# PX4FMUv2_4_6_2.net
KiCad netlist of a schematic drawn in Altium Designer
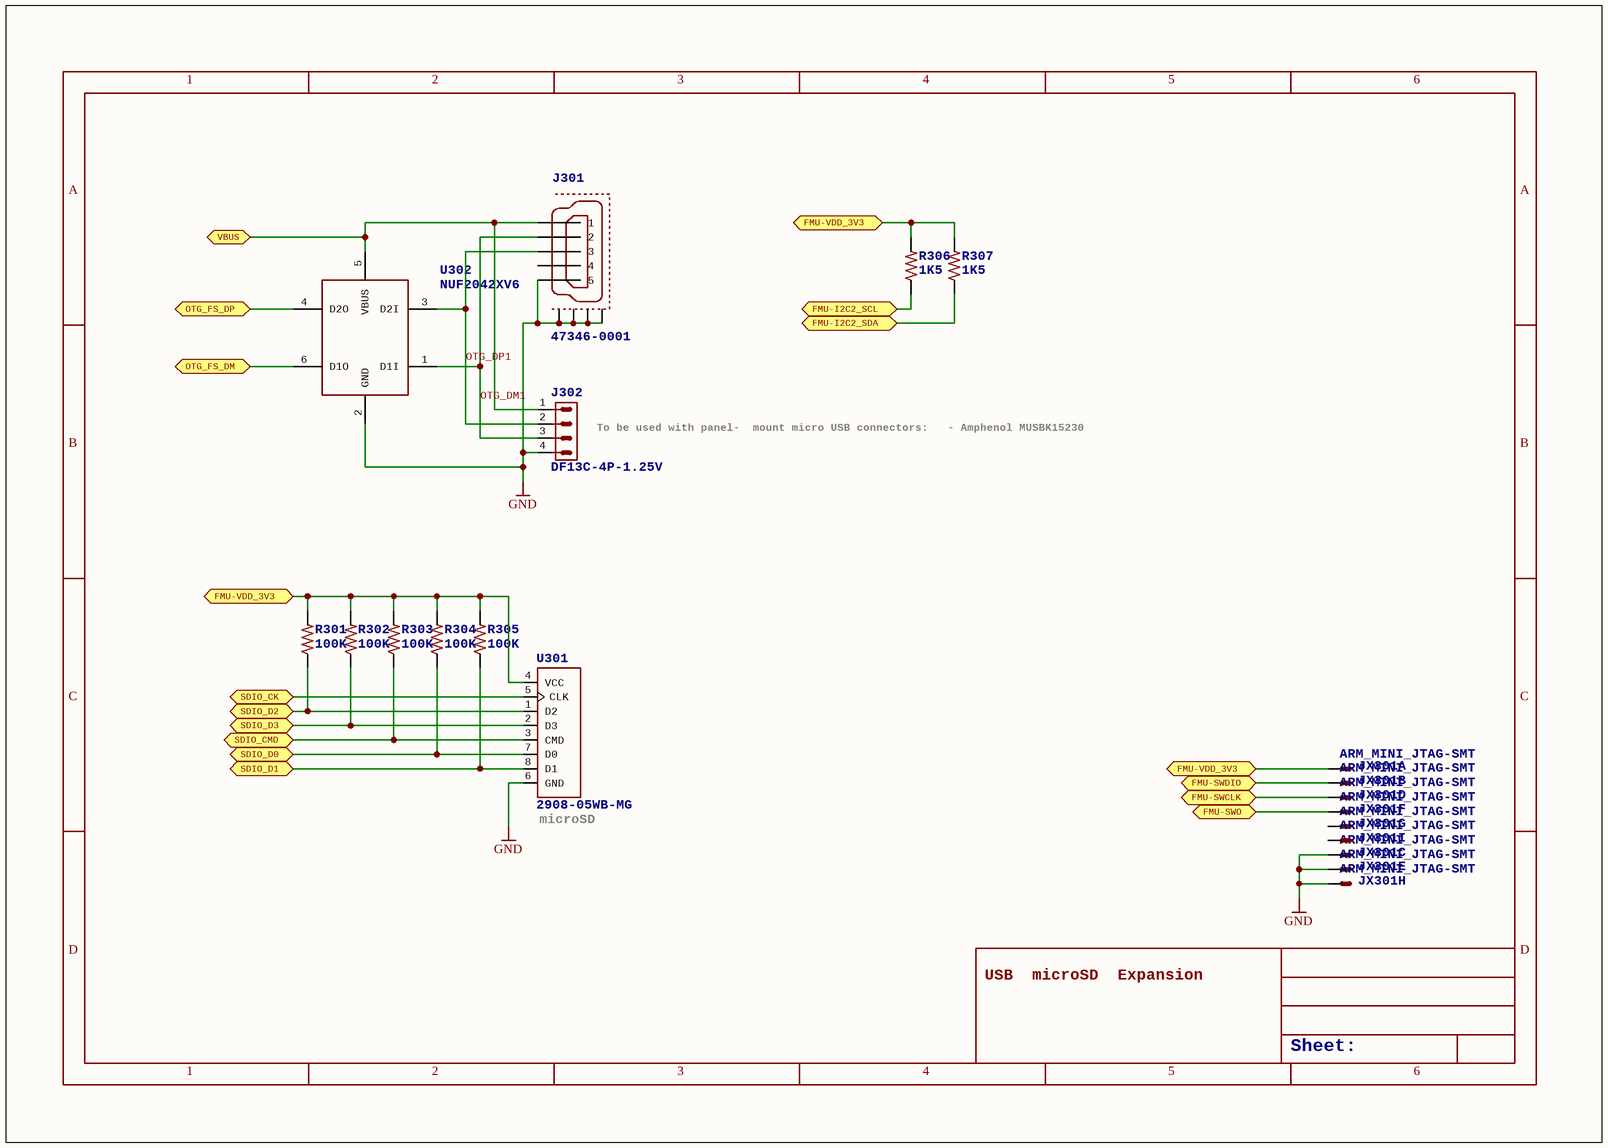
[diagram p0: PX4FMUv2.4.6_2.SchDoc]

(export (version "E")
  (design (tool "Eeschema 10.0.6"))
  (components
    (comp (ref "J301")
      (value "47346-0001")
      (footprint "MOLEX-47346-0001")
      (description "MICRO USB B, BOTTOM MOUNT")
      (libsource (lib "pixhawk2") (part "MOLEX-47346-0001"))
    )
    (comp (ref "J302")
      (value "DF13C-4P-1.25V")
      (footprint "DF13C-4P-1.25V")
      (description "DF13-4P 1.25mm Pitch Miniature Crimping Connector.")
      (fields (field (name "PARTNO") "DF13C-4P-1.25V(20)"))
      (libsource (lib "con-hirose-df13") (part "DF13-4P-1.25V"))
    )
    (comp (ref "JX301")
      (value "ARM_MINI_JTAG-SMT")
      (footprint "FTSH-105-01-XXX-DV-K")
      (description "CONNECTOR   wire to board 1.25 mm (.049 inch) pitch header")
      (fields (field (name "PARTNO") "M50-3900542"))
      (libsource (lib "pixhawk2") (part "ARM_MINI_JTAG-SMT"))
    )
    (comp (ref "R301")
      (value "100K")
      (footprint "0402-RES")
      (fields (field (name "PARTNO") "RC0402FR-07100KL"))
      (libsource (lib "pixhawk2") (part "RESISTOR0402-RES"))
    )
    (comp (ref "R302")
      (value "100K")
      (footprint "0402-RES")
      (fields (field (name "PARTNO") "RC0402FR-07100KL"))
      (libsource (lib "pixhawk2") (part "RESISTOR0402-RES"))
    )
    (comp (ref "R303")
      (value "100K")
      (footprint "0402-RES")
      (fields (field (name "PARTNO") "RC0402FR-07100KL"))
      (libsource (lib "pixhawk2") (part "RESISTOR0402-RES"))
    )
    (comp (ref "R304")
      (value "100K")
      (footprint "0402-RES")
      (fields (field (name "PARTNO") "RC0402FR-07100KL"))
      (libsource (lib "pixhawk2") (part "RESISTOR0402-RES"))
    )
    (comp (ref "R305")
      (value "100K")
      (footprint "0402-RES")
      (fields (field (name "PARTNO") "RC0402FR-07100KL"))
      (libsource (lib "pixhawk2") (part "RESISTOR0402-RES"))
    )
    (comp (ref "R306")
      (value "1K5")
      (footprint "0402-RES")
      (fields (field (name "PARTNO") "RC0402FR-071K5L"))
      (libsource (lib "pixhawk2") (part "RESISTOR0402-RES"))
    )
    (comp (ref "R307")
      (value "1K5")
      (footprint "0402-RES")
      (fields (field (name "PARTNO") "RC0402FR-071K5L"))
      (libsource (lib "pixhawk2") (part "RESISTOR0402-RES"))
    )
    (comp (ref "U301")
      (value "2908-05WB-MG")
      (footprint "MICROSD")
      (libsource (lib "baseboard") (part "MICROSDSDI"))
    )
    (comp (ref "U302")
      (value "NUF2042XV6")
      (footprint "SOT563-6")
      (fields (field (name "PARTNO") "NUF2042XV6T1G"))
      (libsource (lib "pixhawk2") (part "NUF2042XV6"))
    )
  )
  (nets
    (net (code "1") (name "/FMU-I2C2_SCL") (class "Default")
      (node (ref "R306") (pin "P$1") (pinfunction "1_P$1") (pintype "passive"))
    )
    (net (code "2") (name "/FMU-I2C2_SDA") (class "Default")
      (node (ref "R307") (pin "P$1") (pinfunction "1_P$1") (pintype "passive"))
    )
    (net (code "3") (name "/FMU-SWCLK") (class "Default")
      (node (ref "JX301") (pin "4") (pinfunction "S_4") (pintype "passive"))
    )
    (net (code "4") (name "/FMU-SWDIO") (class "Default")
      (node (ref "JX301") (pin "2") (pinfunction "S_2") (pintype "passive"))
    )
    (net (code "5") (name "/FMU-SWO") (class "Default")
      (node (ref "JX301") (pin "6") (pinfunction "S_6") (pintype "passive"))
    )
    (net (code "6") (name "/FMU-VDD_3V3") (class "Default")
      (node (ref "JX301") (pin "1") (pinfunction "S_1") (pintype "passive"))
      (node (ref "R301") (pin "P$2") (pinfunction "2_P$2") (pintype "passive"))
      (node (ref "R302") (pin "P$2") (pinfunction "2_P$2") (pintype "passive"))
      (node (ref "R303") (pin "P$2") (pinfunction "2_P$2") (pintype "passive"))
      (node (ref "R304") (pin "P$2") (pinfunction "2_P$2") (pintype "passive"))
      (node (ref "R305") (pin "P$2") (pinfunction "2_P$2") (pintype "passive"))
      (node (ref "R306") (pin "P$2") (pinfunction "2_P$2") (pintype "passive"))
      (node (ref "R307") (pin "P$2") (pinfunction "2_P$2") (pintype "passive"))
      (node (ref "U301") (pin "4") (pinfunction "VCC_4") (pintype "passive"))
    )
    (net (code "7") (name "/OTG_DM1") (class "Default")
      (node (ref "J301") (pin "D-") (pinfunction "2_D-") (pintype "passive"))
      (node (ref "J302") (pin "3") (pinfunction "3_3") (pintype "passive"))
      (node (ref "U302") (pin "1") (pinfunction "D1I_1") (pintype "passive"))
    )
    (net (code "8") (name "/OTG_DP1") (class "Default")
      (node (ref "J301") (pin "D+") (pinfunction "3_D+") (pintype "passive"))
      (node (ref "J302") (pin "2") (pinfunction "2_2") (pintype "passive"))
      (node (ref "U302") (pin "3") (pinfunction "D2I_3") (pintype "passive"))
    )
    (net (code "9") (name "/OTG_FS_DM") (class "Default")
      (node (ref "U302") (pin "6") (pinfunction "D1O_6") (pintype "passive"))
    )
    (net (code "10") (name "/OTG_FS_DP") (class "Default")
      (node (ref "U302") (pin "4") (pinfunction "D2O_4") (pintype "passive"))
    )
    (net (code "11") (name "/SDIO_CK") (class "Default")
      (node (ref "U301") (pin "5") (pinfunction "CLK_5") (pintype "passive"))
    )
    (net (code "12") (name "/SDIO_CMD") (class "Default")
      (node (ref "R303") (pin "P$1") (pinfunction "1_P$1") (pintype "passive"))
      (node (ref "U301") (pin "3") (pinfunction "CMD_3") (pintype "passive"))
    )
    (net (code "13") (name "/SDIO_D0") (class "Default")
      (node (ref "R304") (pin "P$1") (pinfunction "1_P$1") (pintype "passive"))
      (node (ref "U301") (pin "7") (pinfunction "D0_7") (pintype "passive"))
    )
    (net (code "14") (name "/SDIO_D1") (class "Default")
      (node (ref "R305") (pin "P$1") (pinfunction "1_P$1") (pintype "passive"))
      (node (ref "U301") (pin "8") (pinfunction "D1_8") (pintype "passive"))
    )
    (net (code "15") (name "/SDIO_D2") (class "Default")
      (node (ref "R301") (pin "P$1") (pinfunction "1_P$1") (pintype "passive"))
      (node (ref "U301") (pin "1") (pinfunction "D2_1") (pintype "passive"))
    )
    (net (code "16") (name "/SDIO_D3") (class "Default")
      (node (ref "R302") (pin "P$1") (pinfunction "1_P$1") (pintype "passive"))
      (node (ref "U301") (pin "2") (pinfunction "D3_2") (pintype "passive"))
    )
    (net (code "17") (name "/VBUS") (class "Default")
      (node (ref "J301") (pin "VBUS") (pinfunction "1_VBUS") (pintype "open_emitter"))
      (node (ref "J302") (pin "1") (pinfunction "1_1") (pintype "passive"))
      (node (ref "U302") (pin "5") (pinfunction "VBUS_5") (pintype "passive"))
    )
    (net (code "18") (name "GND") (class "Default")
      (node (ref "J301") (pin "GND") (pinfunction "5_GND") (pintype "open_emitter"))
      (node (ref "J301") (pin "GND1") (pinfunction "GND1_GND1") (pintype "passive"))
      (node (ref "J301") (pin "GND2") (pinfunction "GND2_GND2") (pintype "passive"))
      (node (ref "J301") (pin "GND3") (pinfunction "GND3_GND3") (pintype "passive"))
      (node (ref "J301") (pin "GND4") (pinfunction "GND4_GND4") (pintype "passive"))
      (node (ref "J302") (pin "4") (pinfunction "4_4") (pintype "passive"))
      (node (ref "JX301") (pin "3") (pinfunction "S_3") (pintype "passive"))
      (node (ref "JX301") (pin "5") (pinfunction "S_5") (pintype "passive"))
      (node (ref "JX301") (pin "9") (pinfunction "S_9") (pintype "passive"))
      (node (ref "U301") (pin "6") (pinfunction "GND_6") (pintype "open_emitter"))
      (node (ref "U302") (pin "2") (pinfunction "GND_2") (pintype "passive"))
    )
    (net (code "19") (name "unconnected-(J301-4-PadID)") (class "Default")
      (node (ref "J301") (pin "ID") (pinfunction "4_ID") (pintype "passive"))
    )
    (net (code "20") (name "unconnected-(JX301G-S-Pad8)") (class "Default")
      (node (ref "JX301") (pin "8") (pinfunction "S_8") (pintype "passive"))
    )
    (net (code "21") (name "unconnected-(JX301I-S-Pad10)") (class "Default")
      (node (ref "JX301") (pin "10") (pinfunction "S_10") (pintype "passive"))
    )
  )
)
